# schematics.net
KiCad netlist of a schematic drawn in EasyEDA
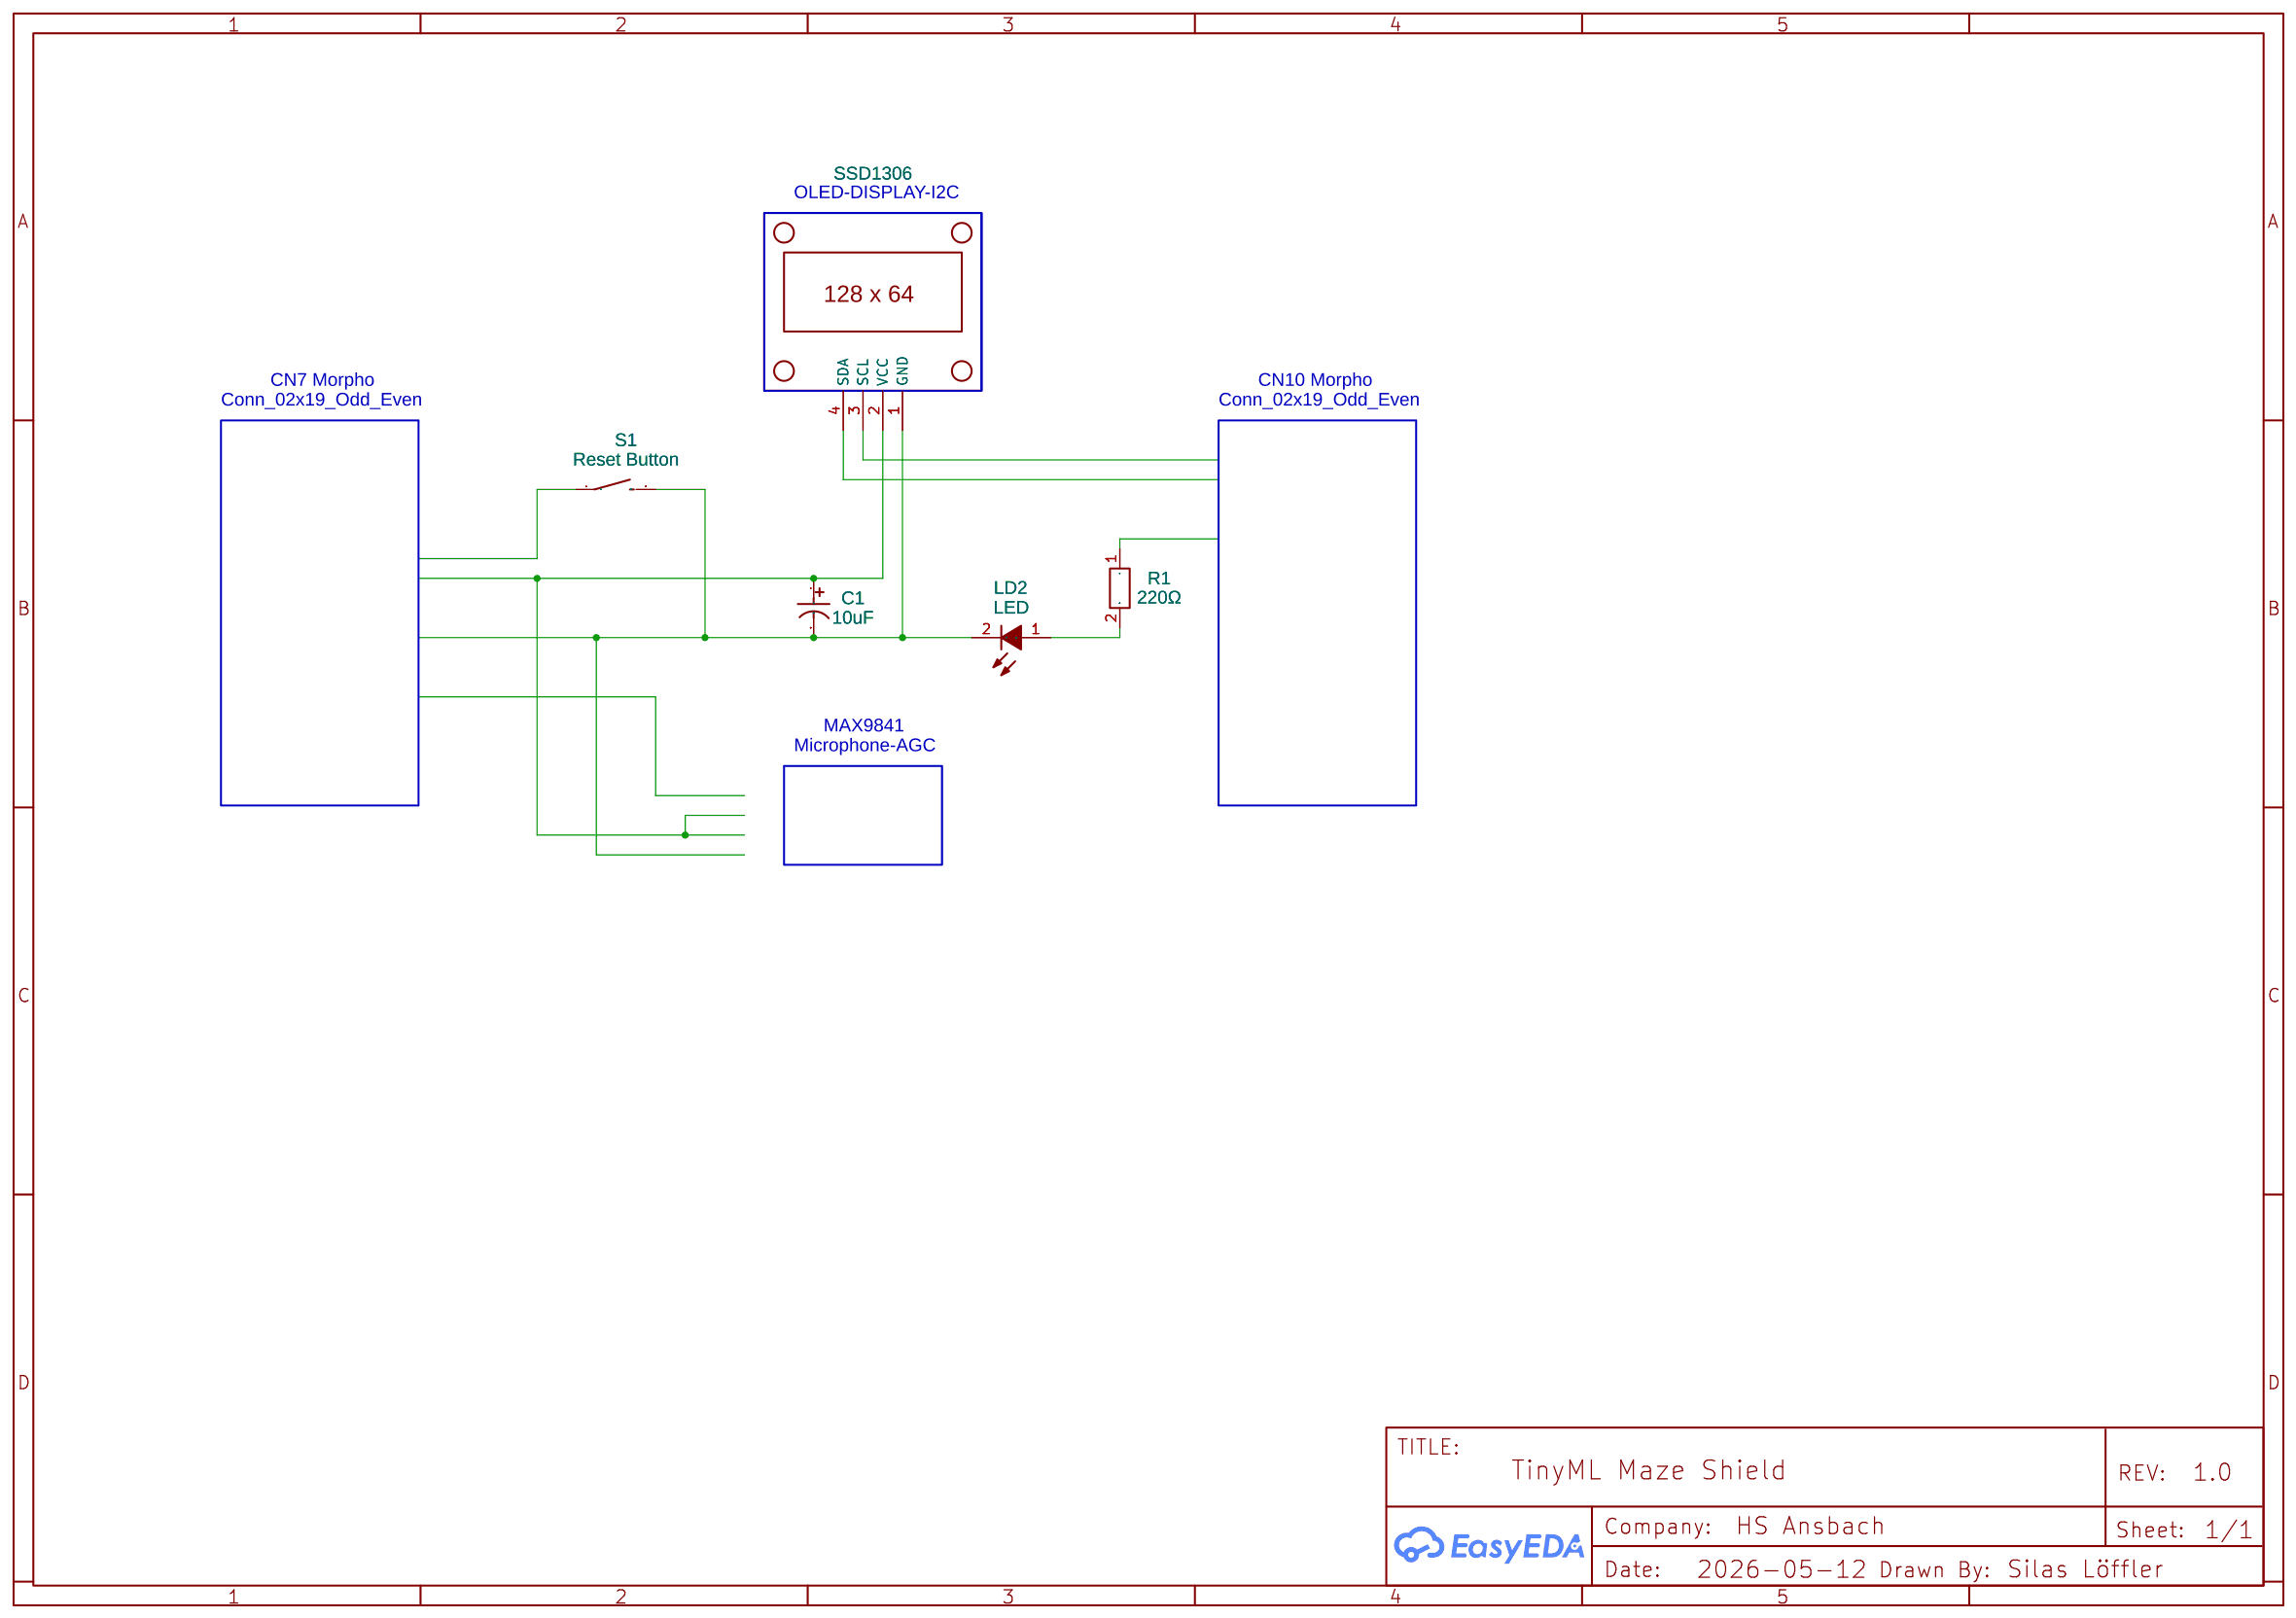
[diagram p0: schematic sheet]

(export (version "E")
  (design (tool "Eeschema 10.0.6"))
  (components
    (comp (ref "C1")
      (value "10uF")
      (fields
        (field (name "Manufacturer Part") "electrolytic capacitor10UF50V")
        (field (name "Manufacturer") "ValuePro")
      )
      (libsource (lib "") (part "ELCO 10UF 50V _DEXTER"))
    )
    (comp (ref "LCD1") (value "SSD1306") (libsource (lib "") (part "SSD1306-OLED-128X64-I2C-NOHOLES")))
    (comp (ref "LD2")
      (value "LED")
      (fields (field (name "Manufacturer Part") "5600") (field (name "Manufacturer") "VccLite"))
      (libsource (lib "") (part "LED"))
    )
    (comp (ref "R1") (value "220Ω") (libsource (lib "") (part "220Ω-RESISTOR")))
    (comp (ref "S1")
      (value "Reset Button")
      (fields (field (name "Manufacturer Part") "X"))
      (libsource (lib "") (part "SWITCH"))
    )
  )
  (nets
    (net (code "1") (name "Net-(LCD1-GND)") (class "Default")
      (node (ref "C1") (pin "2") (pinfunction "2_2") (pintype "input"))
      (node (ref "LCD1") (pin "1") (pinfunction "GND_1") (pintype "unspecified"))
      (node (ref "LD2") (pin "2") (pinfunction "K_2") (pintype "unspecified"))
      (node (ref "S1") (pin "2") (pinfunction "2_2") (pintype "unspecified"))
    )
    (net (code "2") (name "Net-(LCD1-VCC)") (class "Default")
      (node (ref "C1") (pin "1") (pinfunction "1_1") (pintype "input"))
      (node (ref "LCD1") (pin "2") (pinfunction "VCC_2") (pintype "unspecified"))
    )
    (net (code "3") (name "Net-(LD2-A)") (class "Default")
      (node (ref "LD2") (pin "1") (pinfunction "A_1") (pintype "unspecified"))
      (node (ref "R1") (pin "2") (pinfunction "2_2") (pintype "unspecified"))
    )
    (net (code "4") (name "unconnected-(LCD1-SCL-Pad3)") (class "Default")
      (node (ref "LCD1") (pin "3") (pinfunction "SCL_3") (pintype "unspecified"))
    )
    (net (code "5") (name "unconnected-(LCD1-SDA-Pad4)") (class "Default")
      (node (ref "LCD1") (pin "4") (pinfunction "SDA_4") (pintype "unspecified"))
    )
    (net (code "6") (name "unconnected-(R1-Pad1)") (class "Default")
      (node (ref "R1") (pin "1") (pinfunction "1_1") (pintype "unspecified"))
    )
    (net (code "7") (name "unconnected-(S1-Pad1)") (class "Default")
      (node (ref "S1") (pin "1") (pinfunction "1_1") (pintype "unspecified"))
    )
  )
)
